# Screw.net
KiCad netlist of a schematic drawn in EAGLE
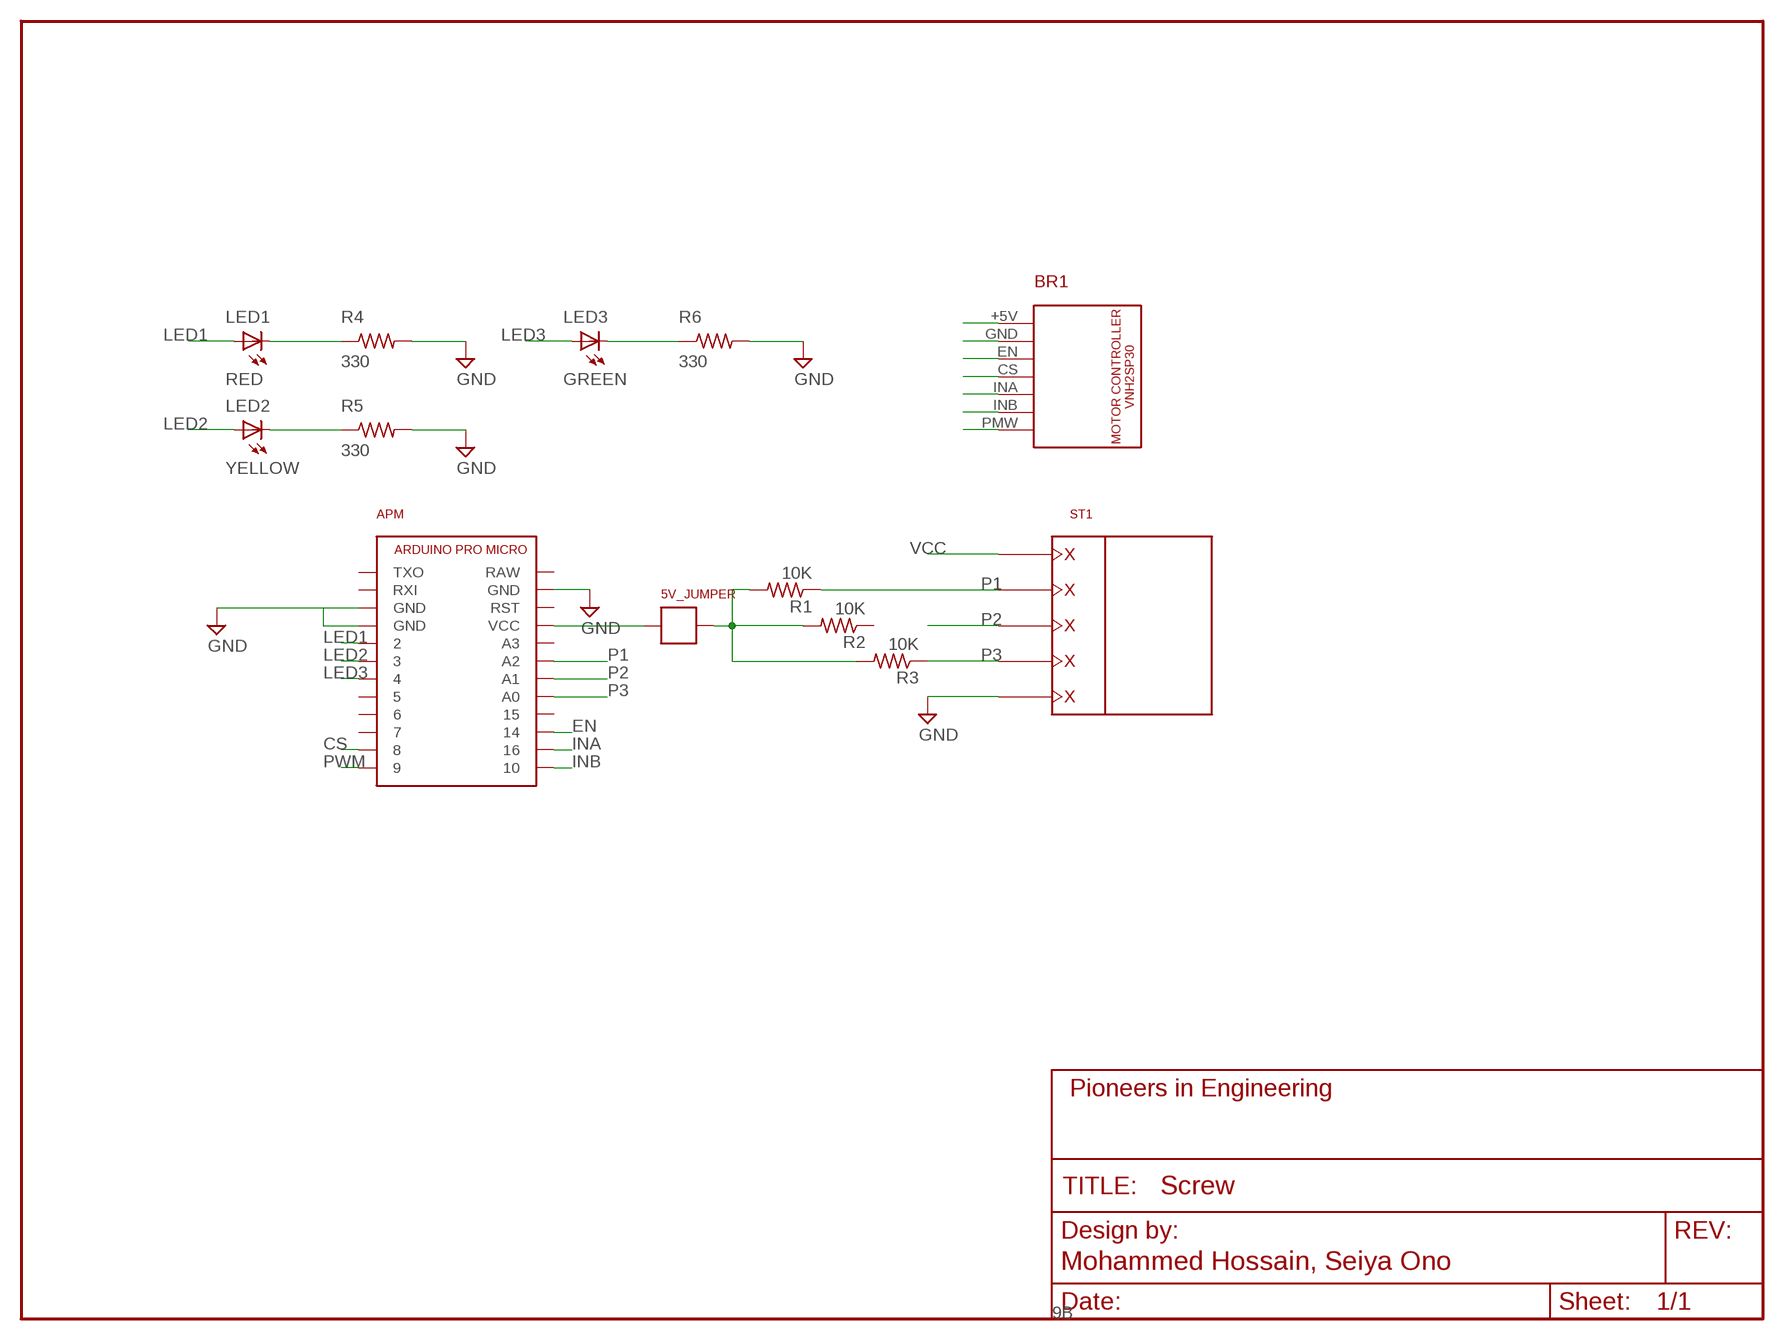
[diagram p0: schematic, sheet 1]

(export (version "E")
  (design (tool "Eeschema 10.0.6"))
  (components
    (comp (ref "5V_JUMPER")
      (value "JUMPER")
      (footprint "eagle-import:JUMPER")
      (libsource (lib "eagle-import") (part "JUMPER"))
    )
    (comp (ref "APM")
      (value "ARDUINO_PRO_MICRO")
      (footprint "eagle-import:ARDUINO_PRO_MICRO")
      (libsource (lib "eagle-import") (part "ARDUINO_PRO_MICRO"))
    )
    (comp (ref "BR1")
      (value "VNH2SP30_MOTOR_CONTROLLER")
      (footprint "eagle-import:VNH2SP30_MOTOR_CONTROLLER")
      (libsource (lib "eagle-import") (part "VNH2SP30_MOTOR_CONTROLLER"))
    )
    (comp (ref "LED1")
      (value "RED")
      (footprint "eagle-import:FKIT-LED-1206")
      (libsource (lib "eagle-import") (part "LED-FKIT-1206"))
    )
    (comp (ref "LED2")
      (value "YELLOW")
      (footprint "eagle-import:FKIT-LED-1206")
      (libsource (lib "eagle-import") (part "LED-FKIT-1206"))
    )
    (comp (ref "LED3")
      (value "GREEN")
      (footprint "eagle-import:FKIT-LED-1206")
      (libsource (lib "eagle-import") (part "LED-FKIT-1206"))
    )
    (comp (ref "R1")
      (value "10K")
      (footprint "eagle-import:R0603")
      (libsource (lib "eagle-import") (part "resistor_R-US_R0603"))
    )
    (comp (ref "R2")
      (value "10K")
      (footprint "eagle-import:R0603")
      (libsource (lib "eagle-import") (part "resistor_R-US_R0603"))
    )
    (comp (ref "R3")
      (value "10K")
      (footprint "eagle-import:R0603")
      (libsource (lib "eagle-import") (part "resistor_R-US_R0603"))
    )
    (comp (ref "R4")
      (value "330")
      (footprint "eagle-import:R0603")
      (libsource (lib "eagle-import") (part "R-US_R0603"))
    )
    (comp (ref "R5")
      (value "330")
      (footprint "eagle-import:R0603")
      (libsource (lib "eagle-import") (part "R-US_R0603"))
    )
    (comp (ref "R6")
      (value "330")
      (footprint "eagle-import:R0603")
      (libsource (lib "eagle-import") (part "R-US_R0603"))
    )
    (comp (ref "ST1")
      (value "5PIN_SCREW")
      (footprint "eagle-import:5PIN_SCREW")
      (libsource (lib "eagle-import") (part "5PIN_SCREW"))
    )
  )
  (nets
    (net (code "1") (name "/CS") (class "Default")
      (node (ref "APM") (pin "8") (pinfunction "8_8") (pintype "bidirectional"))
      (node (ref "BR1") (pin "CS") (pinfunction "CS_CS") (pintype "bidirectional"))
    )
    (net (code "2") (name "/EN") (class "Default")
      (node (ref "APM") (pin "14") (pinfunction "14_14") (pintype "bidirectional"))
      (node (ref "BR1") (pin "EN") (pinfunction "EN_EN") (pintype "bidirectional"))
    )
    (net (code "3") (name "/INA") (class "Default")
      (node (ref "APM") (pin "16") (pinfunction "16_16") (pintype "bidirectional"))
      (node (ref "BR1") (pin "INA") (pinfunction "INA_INA") (pintype "bidirectional"))
    )
    (net (code "4") (name "/INB") (class "Default")
      (node (ref "APM") (pin "10") (pinfunction "10_10") (pintype "bidirectional"))
      (node (ref "BR1") (pin "INB") (pinfunction "INB_INB") (pintype "bidirectional"))
    )
    (net (code "5") (name "/LED1") (class "Default")
      (node (ref "APM") (pin "2") (pinfunction "2_2") (pintype "bidirectional"))
      (node (ref "LED1") (pin "A") (pinfunction "A_A") (pintype "passive"))
    )
    (net (code "6") (name "/LED2") (class "Default")
      (node (ref "APM") (pin "3") (pinfunction "3_3") (pintype "bidirectional"))
      (node (ref "LED2") (pin "A") (pinfunction "A_A") (pintype "passive"))
    )
    (net (code "7") (name "/LED3") (class "Default")
      (node (ref "APM") (pin "4") (pinfunction "4_4") (pintype "bidirectional"))
      (node (ref "LED3") (pin "A") (pinfunction "A_A") (pintype "passive"))
    )
    (net (code "8") (name "/P1") (class "Default")
      (node (ref "APM") (pin "A2") (pinfunction "A2_A2") (pintype "bidirectional"))
      (node (ref "R1") (pin "1") (pinfunction "1_1") (pintype "passive"))
      (node (ref "ST1") (pin "P$2") (pinfunction "P$2_P$2") (pintype "bidirectional"))
    )
    (net (code "9") (name "/P2") (class "Default")
      (node (ref "APM") (pin "A1") (pinfunction "A1_A1") (pintype "bidirectional"))
      (node (ref "ST1") (pin "P$3") (pinfunction "P$3_P$3") (pintype "bidirectional"))
    )
    (net (code "10") (name "/P3") (class "Default")
      (node (ref "APM") (pin "A0") (pinfunction "A0_A0") (pintype "bidirectional"))
      (node (ref "R3") (pin "1") (pinfunction "1_1") (pintype "passive"))
      (node (ref "ST1") (pin "P$4") (pinfunction "P$4_P$4") (pintype "bidirectional"))
    )
    (net (code "11") (name "/PWM") (class "Default")
      (node (ref "APM") (pin "9") (pinfunction "9_9") (pintype "bidirectional"))
      (node (ref "BR1") (pin "PMW") (pinfunction "PMW_PMW") (pintype "bidirectional"))
    )
    (net (code "12") (name "/VCC") (class "Default")
      (node (ref "5V_JUMPER") (pin "P$1") (pinfunction "P$1_P$1") (pintype "input"))
      (node (ref "APM") (pin "VCC") (pinfunction "VCC_VCC") (pintype "bidirectional"))
      (node (ref "BR1") (pin "+5V") (pinfunction "+5V_+5V") (pintype "bidirectional"))
      (node (ref "ST1") (pin "P$1") (pinfunction "P$1_P$1") (pintype "bidirectional"))
    )
    (net (code "13") (name "GND") (class "Default")
      (node (ref "APM") (pin "GND@0") (pinfunction "GND_GND@0") (pintype "bidirectional"))
      (node (ref "APM") (pin "GND@1") (pinfunction "GND_GND@1") (pintype "bidirectional"))
      (node (ref "APM") (pin "GND@2") (pinfunction "GND_GND@2") (pintype "bidirectional"))
      (node (ref "BR1") (pin "GND") (pinfunction "GND_GND") (pintype "bidirectional"))
      (node (ref "R4") (pin "2") (pinfunction "2_2") (pintype "passive"))
      (node (ref "R5") (pin "2") (pinfunction "2_2") (pintype "passive"))
      (node (ref "R6") (pin "2") (pinfunction "2_2") (pintype "passive"))
      (node (ref "ST1") (pin "P$5") (pinfunction "P$5_P$5") (pintype "bidirectional"))
    )
    (net (code "14") (name "Net-(5V_JUMPER-PadP$2)") (class "Default")
      (node (ref "5V_JUMPER") (pin "P$2") (pinfunction "P$2_P$2") (pintype "bidirectional"))
      (node (ref "R1") (pin "2") (pinfunction "2_2") (pintype "passive"))
      (node (ref "R2") (pin "2") (pinfunction "2_2") (pintype "passive"))
      (node (ref "R3") (pin "2") (pinfunction "2_2") (pintype "passive"))
    )
    (net (code "15") (name "Net-(LED1-PadC)") (class "Default")
      (node (ref "LED1") (pin "C") (pinfunction "C_C") (pintype "passive"))
      (node (ref "R4") (pin "1") (pinfunction "1_1") (pintype "passive"))
    )
    (net (code "16") (name "Net-(LED2-PadC)") (class "Default")
      (node (ref "LED2") (pin "C") (pinfunction "C_C") (pintype "passive"))
      (node (ref "R5") (pin "1") (pinfunction "1_1") (pintype "passive"))
    )
    (net (code "17") (name "Net-(LED3-PadC)") (class "Default")
      (node (ref "LED3") (pin "C") (pinfunction "C_C") (pintype "passive"))
      (node (ref "R6") (pin "1") (pinfunction "1_1") (pintype "passive"))
    )
    (net (code "18") (name "unconnected-(APM-Pad5)") (class "Default")
      (node (ref "APM") (pin "5") (pinfunction "5_5") (pintype "bidirectional"))
    )
    (net (code "19") (name "unconnected-(APM-Pad6)") (class "Default")
      (node (ref "APM") (pin "6") (pinfunction "6_6") (pintype "bidirectional"))
    )
    (net (code "20") (name "unconnected-(APM-Pad7)") (class "Default")
      (node (ref "APM") (pin "7") (pinfunction "7_7") (pintype "bidirectional"))
    )
    (net (code "21") (name "unconnected-(APM-Pad15)") (class "Default")
      (node (ref "APM") (pin "15") (pinfunction "15_15") (pintype "bidirectional"))
    )
    (net (code "22") (name "unconnected-(APM-PadA3)") (class "Default")
      (node (ref "APM") (pin "A3") (pinfunction "A3_A3") (pintype "bidirectional"))
    )
    (net (code "23") (name "unconnected-(APM-PadRAW)") (class "Default")
      (node (ref "APM") (pin "RAW") (pinfunction "RAW_RAW") (pintype "bidirectional"))
    )
    (net (code "24") (name "unconnected-(APM-PadRST)") (class "Default")
      (node (ref "APM") (pin "RST") (pinfunction "RST_RST") (pintype "bidirectional"))
    )
    (net (code "25") (name "unconnected-(APM-PadRXI)") (class "Default")
      (node (ref "APM") (pin "RXI") (pinfunction "RXI_RXI") (pintype "bidirectional"))
    )
    (net (code "26") (name "unconnected-(APM-PadTXO)") (class "Default")
      (node (ref "APM") (pin "TXO") (pinfunction "TXO_TXO") (pintype "bidirectional"))
    )
    (net (code "27") (name "unconnected-(R2-Pad1)") (class "Default")
      (node (ref "R2") (pin "1") (pinfunction "1_1") (pintype "passive"))
    )
  )
)
